# STPedal_Power.net
KiCad netlist of a schematic drawn in Altium Designer
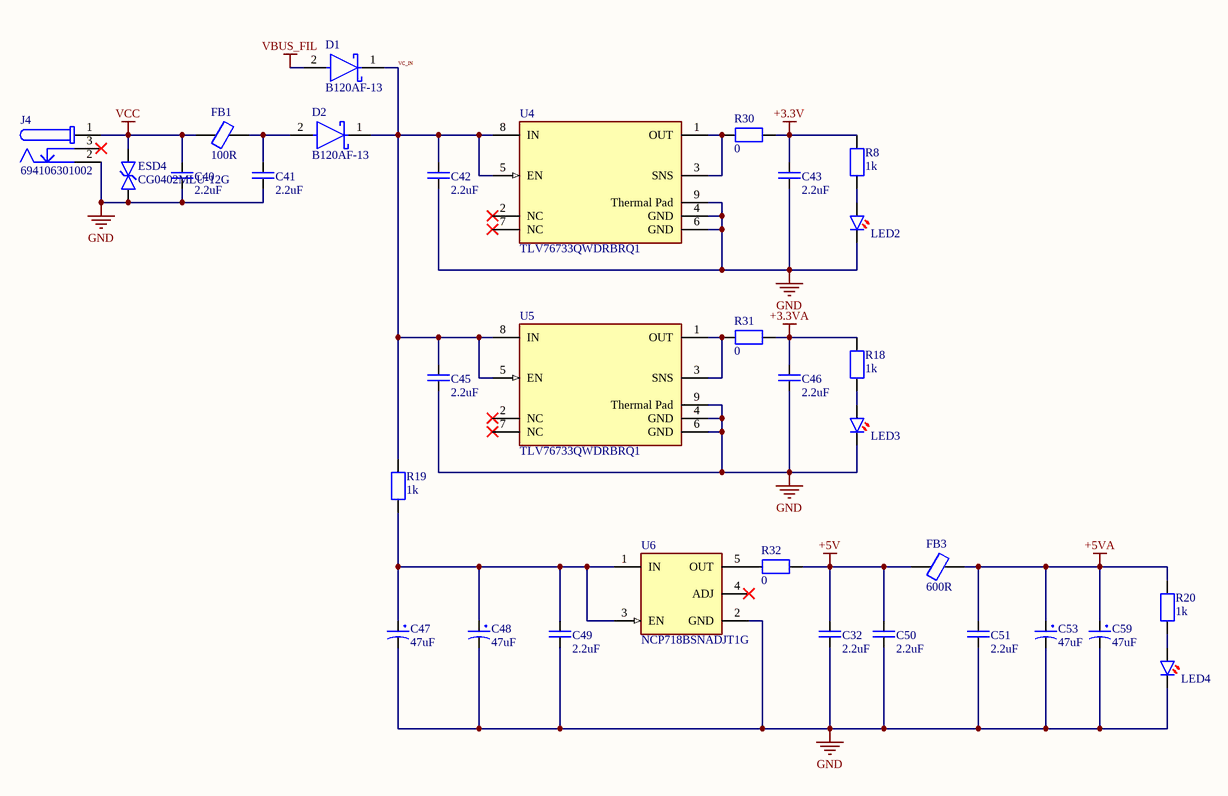
[diagram p0: STPedal_Power.SchDoc]

(export (version "E")
  (design (tool "Eeschema 10.0.6"))
  (components
    (comp (ref "C32")
      (value "2.2uF")
      (footprint "CAPC_0402_1005X55N")
      (description "Capacitor 0402 - 2.2uF +-/10% / 25V")
      (fields
        (field (name "MANUFACTURER") "Samsung Electro-Mechanics")
        (field (name "MPN") "CL05A225MQ5NSNC")
      )
      (libsource (lib "ReekoLib") (part "2.2uF_CAP_0402"))
    )
    (comp (ref "C40")
      (value "2.2uF")
      (footprint "CAPC_0402_1005X55N")
      (description "Capacitor 0402 - 2.2uF +-/10% / 25V")
      (fields
        (field (name "MANUFACTURER") "Samsung Electro-Mechanics")
        (field (name "MPN") "CL05A225MQ5NSNC")
      )
      (libsource (lib "ReekoLib") (part "2.2uF_CAP_0402"))
    )
    (comp (ref "C41")
      (value "2.2uF")
      (footprint "CAPC_0402_1005X55N")
      (description "Capacitor 0402 - 2.2uF +-/10% / 25V")
      (fields
        (field (name "MANUFACTURER") "Samsung Electro-Mechanics")
        (field (name "MPN") "CL05A225MQ5NSNC")
      )
      (libsource (lib "ReekoLib") (part "2.2uF_CAP_0402"))
    )
    (comp (ref "C42")
      (value "2.2uF")
      (footprint "CAPC_0402_1005X55N")
      (description "Capacitor 0402 - 2.2uF +-/10% / 25V")
      (fields
        (field (name "MANUFACTURER") "Samsung Electro-Mechanics")
        (field (name "MPN") "CL05A225MQ5NSNC")
      )
      (libsource (lib "ReekoLib") (part "2.2uF_CAP_0402"))
    )
    (comp (ref "C43")
      (value "2.2uF")
      (footprint "CAPC_0402_1005X55N")
      (description "Capacitor 0402 - 2.2uF +-/10% / 25V")
      (fields
        (field (name "MANUFACTURER") "Samsung Electro-Mechanics")
        (field (name "MPN") "CL05A225MQ5NSNC")
      )
      (libsource (lib "ReekoLib") (part "2.2uF_CAP_0402"))
    )
    (comp (ref "C45")
      (value "2.2uF")
      (footprint "CAPC_0402_1005X55N")
      (description "Capacitor 0402 - 2.2uF +-/10% / 25V")
      (fields
        (field (name "MANUFACTURER") "Samsung Electro-Mechanics")
        (field (name "MPN") "CL05A225MQ5NSNC")
      )
      (libsource (lib "ReekoLib") (part "2.2uF_CAP_0402"))
    )
    (comp (ref "C46")
      (value "2.2uF")
      (footprint "CAPC_0402_1005X55N")
      (description "Capacitor 0402 - 2.2uF +-/10% / 25V")
      (fields
        (field (name "MANUFACTURER") "Samsung Electro-Mechanics")
        (field (name "MPN") "CL05A225MQ5NSNC")
      )
      (libsource (lib "ReekoLib") (part "2.2uF_CAP_0402"))
    )
    (comp (ref "C47")
      (value "47uF")
      (footprint "SMD,D6.3xL5.4mm")
      (fields (field (name "MPN") "RVT1V470M0605"))
      (libsource (lib "ReekoLib") (part "47uF_JLCAP_Elect_D6.3mm"))
    )
    (comp (ref "C48")
      (value "47uF")
      (footprint "SMD,D6.3xL5.4mm")
      (fields (field (name "MPN") "RVT1V470M0605"))
      (libsource (lib "ReekoLib") (part "47uF_JLCAP_Elect_D6.3mm"))
    )
    (comp (ref "C49")
      (value "2.2uF")
      (footprint "CAPC_0402_1005X55N")
      (description "Capacitor 0402 - 2.2uF +-/10% / 25V")
      (fields
        (field (name "MANUFACTURER") "Samsung Electro-Mechanics")
        (field (name "MPN") "CL05A225MQ5NSNC")
      )
      (libsource (lib "ReekoLib") (part "2.2uF_CAP_0402"))
    )
    (comp (ref "C50")
      (value "2.2uF")
      (footprint "CAPC_0402_1005X55N")
      (description "Capacitor 0402 - 2.2uF +-/10% / 25V")
      (fields
        (field (name "MANUFACTURER") "Samsung Electro-Mechanics")
        (field (name "MPN") "CL05A225MQ5NSNC")
      )
      (libsource (lib "ReekoLib") (part "2.2uF_CAP_0402"))
    )
    (comp (ref "C51")
      (value "2.2uF")
      (footprint "CAPC_0402_1005X55N")
      (description "Capacitor 0402 - 2.2uF +-/10% / 25V")
      (fields
        (field (name "MANUFACTURER") "Samsung Electro-Mechanics")
        (field (name "MPN") "CL05A225MQ5NSNC")
      )
      (libsource (lib "ReekoLib") (part "2.2uF_CAP_0402"))
    )
    (comp (ref "C53")
      (value "47uF")
      (footprint "SMD,D6.3xL5.4mm")
      (fields (field (name "MPN") "RVT1V470M0605"))
      (libsource (lib "ReekoLib") (part "47uF_JLCAP_Elect_D6.3mm"))
    )
    (comp (ref "C59")
      (value "47uF")
      (footprint "SMD,D6.3xL5.4mm")
      (fields (field (name "MPN") "RVT1V470M0605"))
      (libsource (lib "ReekoLib") (part "47uF_JLCAP_Elect_D6.3mm"))
    )
    (comp (ref "D1")
      (value "B120AF-13")
      (footprint "FP-SMAF-MFG")
      (description "DIODE SCHOTTKY 20V 1A SMAF")
      (libsource (lib "Altium Content Vault") (part "1d6ec82d83fb6aee721767c19dac4b9"))
    )
    (comp (ref "D2")
      (value "B120AF-13")
      (footprint "FP-SMAF-MFG")
      (description "DIODE SCHOTTKY 20V 1A SMAF")
      (libsource (lib "Altium Content Vault") (part "1d6ec82d83fb6aee721767c19dac4b9"))
    )
    (comp (ref "ESD4")
      (value "CG0402MLU-12G")
      (footprint "DIOC_0402_1005X41N")
      (description "-40℃~+125℃ 0.05pF 1 12V 25V 5nA ESD IEC 61000-4-2 0402 ESD and Surge Protection (TVS/ESD) ROHS")
      (fields (field (name "MANUFACTURER") "BOURNS"))
      (libsource (lib "ReekoLib") (part "CG0402MLU-12G"))
    )
    (comp (ref "FB1")
      (value "100R")
      (footprint "FBC_0805_2012X105N")
      (description "-55℃~+125℃ 1 300mΩ 500mA 600Ω@100MHz ±25% 0805 Ferrite Beads ROHS")
      (fields (field (name "MANUFACTURER") "Sunlord") (field (name "MPN") "GZ2012D601TF"))
      (libsource (lib "ReekoLib") (part "600@100MHz_JLCFB_0805"))
    )
    (comp (ref "FB3")
      (value "600R")
      (footprint "FBC_0805_2012X105N")
      (description "-55℃~+125℃ 1 300mΩ 500mA 600Ω@100MHz ±25% 0805 Ferrite Beads ROHS")
      (fields (field (name "MANUFACTURER") "Sunlord") (field (name "MPN") "GZ2012D601TF"))
      (libsource (lib "ReekoLib") (part "600@100MHz_JLCFB_0805"))
    )
    (comp (ref "J4")
      (value "694106301002")
      (footprint "694106301002")
      (description "DC Power Jack Connector WR-DC, Male, Right Angled, THT, 5 A, 24 V")
      (libsource (lib "Altium Content Vault") (part "DC Power Jack"))
    )
    (comp (ref "LED2")
      (value "LED_Red_JLCD_0603")
      (footprint "LED_0603_1608")
      (fields (field (name "MANUFACTURER") "Hubei KENTO Elec") (field (name "MPN") "KT-0603R"))
      (libsource (lib "ReekoLib") (part "LED_Red_JLCD_0603"))
    )
    (comp (ref "LED3")
      (value "LED_Red_JLCD_0603")
      (footprint "LED_0603_1608")
      (fields (field (name "MANUFACTURER") "Hubei KENTO Elec") (field (name "MPN") "KT-0603R"))
      (libsource (lib "ReekoLib") (part "LED_Red_JLCD_0603"))
    )
    (comp (ref "LED4")
      (value "LED_Red_JLCD_0603")
      (footprint "LED_0603_1608")
      (fields (field (name "MANUFACTURER") "Hubei KENTO Elec") (field (name "MPN") "KT-0603R"))
      (libsource (lib "ReekoLib") (part "LED_Red_JLCD_0603"))
    )
    (comp (ref "R8")
      (value "1k")
      (footprint "RESC_0402_1005X40N")
      (description "Resistor 0402 - 1k")
      (fields (field (name "MANUFACTURER") "UNI-ROYAL(Uniroyal Elec)") (field (name "MPN") "0402WGF1001TCE"))
      (libsource (lib "ReekoLib") (part "1k_JLCRES-0402"))
    )
    (comp (ref "R18")
      (value "1k")
      (footprint "RESC_0402_1005X40N")
      (description "Resistor 0402 - 1k")
      (fields (field (name "MANUFACTURER") "UNI-ROYAL(Uniroyal Elec)") (field (name "MPN") "0402WGF1001TCE"))
      (libsource (lib "ReekoLib") (part "1k_JLCRES-0402"))
    )
    (comp (ref "R19")
      (value "1k")
      (footprint "RESC_0402_1005X40N")
      (description "Resistor 0402 - 100R")
      (libsource (lib "ReekoLib") (part "100R_JLCRES-0402"))
    )
    (comp (ref "R20")
      (value "1k")
      (footprint "RESC_0402_1005X40N")
      (description "Resistor 0402 - 1k")
      (fields (field (name "MANUFACTURER") "UNI-ROYAL(Uniroyal Elec)") (field (name "MPN") "0402WGF1001TCE"))
      (libsource (lib "ReekoLib") (part "1k_JLCRES-0402"))
    )
    (comp (ref "R30")
      (value "0")
      (footprint "RESC_0402_1005X40N")
      (description "-55℃~+155℃ 0Ω 50V 62.5mW Thick Film Resistor ±1% ±800ppm/℃ 0402 Chip Resistor - Surface Mount ROHS")
      (fields (field (name "MANUFACTURER") "UNI-ROYAL(Uniroyal Elec)") (field (name "MPN") "0402WGF0000TCE"))
      (libsource (lib "ReekoLib") (part "0R_JLCRES-0402"))
    )
    (comp (ref "R31")
      (value "0")
      (footprint "RESC_0402_1005X40N")
      (description "-55℃~+155℃ 0Ω 50V 62.5mW Thick Film Resistor ±1% ±800ppm/℃ 0402 Chip Resistor - Surface Mount ROHS")
      (fields (field (name "MANUFACTURER") "UNI-ROYAL(Uniroyal Elec)") (field (name "MPN") "0402WGF0000TCE"))
      (libsource (lib "ReekoLib") (part "0R_JLCRES-0402"))
    )
    (comp (ref "R32")
      (value "0")
      (footprint "RESC_0402_1005X40N")
      (description "-55℃~+155℃ 0Ω 50V 62.5mW Thick Film Resistor ±1% ±800ppm/℃ 0402 Chip Resistor - Surface Mount ROHS")
      (fields (field (name "MANUFACTURER") "UNI-ROYAL(Uniroyal Elec)") (field (name "MPN") "0402WGF0000TCE"))
      (libsource (lib "ReekoLib") (part "0R_JLCRES-0402"))
    )
    (comp (ref "U4")
      (value "TLV76733QWDRBRQ1")
      (footprint "FP-DRB0008J-IPC_C")
      (description "IC OPAMP")
      (libsource (lib "Altium Content Vault") (part "986f8d1759350ee61d4b04c225c65ee"))
    )
    (comp (ref "U5")
      (value "TLV76733QWDRBRQ1")
      (footprint "FP-DRB0008J-IPC_C")
      (description "IC OPAMP")
      (libsource (lib "Altium Content Vault") (part "986f8d1759350ee61d4b04c225c65ee"))
    )
    (comp (ref "U6")
      (value "NCP718BSNADJT1G")
      (footprint "FP-419AE-01-IPC_C")
      (fields
        (field (name "OCTOPART") "https://octopart.com/ncp718bsnadjt1g-on+semiconductor-87658781")
        (field (name "MANUFACTURER PART NUMBER") "NCP718BSN500T1G")
        (field (name "MANUFACTURER") "On Semiconductor")
      )
      (libsource (lib "Altium Content Vault") (part "60dd149d16d23ee5a651c2107203ec7"))
    )
  )
  (nets
    (net (code "1") (name "+3.3V") (class "Default")
      (node (ref "C43") (pin "2") (pintype "passive"))
      (node (ref "R30") (pin "2") (pintype "passive"))
      (node (ref "R8") (pin "2") (pintype "passive"))
    )
    (net (code "2") (name "+3.3VA") (class "Default")
      (node (ref "C46") (pin "2") (pintype "passive"))
      (node (ref "R18") (pin "2") (pintype "passive"))
      (node (ref "R31") (pin "2") (pintype "passive"))
    )
    (net (code "3") (name "+5V") (class "Default")
      (node (ref "C32") (pin "2") (pintype "passive"))
      (node (ref "C50") (pin "2") (pintype "passive"))
      (node (ref "FB3") (pin "1") (pintype "passive"))
      (node (ref "R32") (pin "2") (pintype "passive"))
    )
    (net (code "4") (name "+5VA") (class "Default")
      (node (ref "C51") (pin "2") (pintype "passive"))
      (node (ref "C53") (pin "1") (pintype "passive"))
      (node (ref "C59") (pin "1") (pintype "passive"))
      (node (ref "FB3") (pin "2") (pintype "passive"))
      (node (ref "R20") (pin "1") (pintype "passive"))
    )
    (net (code "5") (name "/VC_IN") (class "Default")
      (node (ref "C42") (pin "2") (pintype "passive"))
      (node (ref "C45") (pin "2") (pintype "passive"))
      (node (ref "D1") (pin "1") (pinfunction "C_1") (pintype "passive"))
      (node (ref "D2") (pin "1") (pinfunction "C_1") (pintype "passive"))
      (node (ref "R19") (pin "2") (pintype "passive"))
      (node (ref "U4") (pin "5") (pinfunction "EN_5") (pintype "input"))
      (node (ref "U4") (pin "8") (pinfunction "IN_8") (pintype "power_in"))
      (node (ref "U5") (pin "5") (pinfunction "EN_5") (pintype "input"))
      (node (ref "U5") (pin "8") (pinfunction "IN_8") (pintype "power_in"))
    )
    (net (code "6") (name "GND") (class "Default")
      (node (ref "C32") (pin "1") (pintype "passive"))
      (node (ref "C40") (pin "1") (pintype "passive"))
      (node (ref "C41") (pin "1") (pintype "passive"))
      (node (ref "C42") (pin "1") (pintype "passive"))
      (node (ref "C43") (pin "1") (pintype "passive"))
      (node (ref "C45") (pin "1") (pintype "passive"))
      (node (ref "C46") (pin "1") (pintype "passive"))
      (node (ref "C47") (pin "2") (pintype "passive"))
      (node (ref "C48") (pin "2") (pintype "passive"))
      (node (ref "C49") (pin "1") (pintype "passive"))
      (node (ref "C50") (pin "1") (pintype "passive"))
      (node (ref "C51") (pin "1") (pintype "passive"))
      (node (ref "C53") (pin "2") (pintype "passive"))
      (node (ref "C59") (pin "2") (pintype "passive"))
      (node (ref "ESD4") (pin "1") (pintype "passive"))
      (node (ref "J4") (pin "2") (pinfunction "2_2") (pintype "passive"))
      (node (ref "LED2") (pin "2") (pintype "passive"))
      (node (ref "LED3") (pin "2") (pintype "passive"))
      (node (ref "LED4") (pin "2") (pintype "passive"))
      (node (ref "U4") (pin "4") (pinfunction "GND_4") (pintype "power_in"))
      (node (ref "U4") (pin "6") (pinfunction "GND_6") (pintype "power_in"))
      (node (ref "U4") (pin "9") (pinfunction "Thermal_Pad_9") (pintype "passive"))
      (node (ref "U5") (pin "4") (pinfunction "GND_4") (pintype "power_in"))
      (node (ref "U5") (pin "6") (pinfunction "GND_6") (pintype "power_in"))
      (node (ref "U5") (pin "9") (pinfunction "Thermal_Pad_9") (pintype "passive"))
      (node (ref "U6") (pin "2") (pinfunction "GND_2") (pintype "power_in"))
    )
    (net (code "7") (name "Net-(D2-A)") (class "Default")
      (node (ref "C41") (pin "2") (pintype "passive"))
      (node (ref "D2") (pin "2") (pinfunction "A_2") (pintype "passive"))
      (node (ref "FB1") (pin "2") (pintype "passive"))
    )
    (net (code "8") (name "Net-(LED2-Pad1)") (class "Default")
      (node (ref "LED2") (pin "1") (pintype "passive"))
      (node (ref "R8") (pin "1") (pintype "passive"))
    )
    (net (code "9") (name "Net-(LED3-Pad1)") (class "Default")
      (node (ref "LED3") (pin "1") (pintype "passive"))
      (node (ref "R18") (pin "1") (pintype "passive"))
    )
    (net (code "10") (name "Net-(LED4-Pad1)") (class "Default")
      (node (ref "LED4") (pin "1") (pintype "passive"))
      (node (ref "R20") (pin "2") (pintype "passive"))
    )
    (net (code "11") (name "Net-(U4-OUT)") (class "Default")
      (node (ref "R30") (pin "1") (pintype "passive"))
      (node (ref "U4") (pin "1") (pinfunction "OUT_1") (pintype "power_in"))
      (node (ref "U4") (pin "3") (pinfunction "SNS_3") (pintype "passive"))
    )
    (net (code "12") (name "Net-(U5-OUT)") (class "Default")
      (node (ref "R31") (pin "1") (pintype "passive"))
      (node (ref "U5") (pin "1") (pinfunction "OUT_1") (pintype "power_in"))
      (node (ref "U5") (pin "3") (pinfunction "SNS_3") (pintype "passive"))
    )
    (net (code "13") (name "Net-(U6-EN)") (class "Default")
      (node (ref "C47") (pin "1") (pintype "passive"))
      (node (ref "C48") (pin "1") (pintype "passive"))
      (node (ref "C49") (pin "2") (pintype "passive"))
      (node (ref "R19") (pin "1") (pintype "passive"))
      (node (ref "U6") (pin "1") (pinfunction "IN_1") (pintype "power_in"))
      (node (ref "U6") (pin "3") (pinfunction "EN_3") (pintype "input"))
    )
    (net (code "14") (name "Net-(U6-OUT)") (class "Default")
      (node (ref "R32") (pin "1") (pintype "passive"))
      (node (ref "U6") (pin "5") (pinfunction "OUT_5") (pintype "power_in"))
    )
    (net (code "15") (name "VBUS_FIL") (class "Default")
      (node (ref "D1") (pin "2") (pinfunction "A_2") (pintype "passive"))
    )
    (net (code "16") (name "VCC") (class "Default")
      (node (ref "C40") (pin "2") (pintype "passive"))
      (node (ref "ESD4") (pin "2") (pintype "passive"))
      (node (ref "FB1") (pin "1") (pintype "passive"))
      (node (ref "J4") (pin "1") (pinfunction "1_1") (pintype "passive"))
    )
    (net (code "17") (name "unconnected-(J4-Pad3)") (class "Default")
      (node (ref "J4") (pin "3") (pinfunction "3_3") (pintype "passive+no_connect"))
    )
    (net (code "18") (name "unconnected-(U4-NC-Pad2)") (class "Default")
      (node (ref "U4") (pin "2") (pinfunction "NC_2") (pintype "passive+no_connect"))
    )
    (net (code "19") (name "unconnected-(U4-NC-Pad7)") (class "Default")
      (node (ref "U4") (pin "7") (pinfunction "NC_7") (pintype "passive+no_connect"))
    )
    (net (code "20") (name "unconnected-(U5-NC-Pad2)") (class "Default")
      (node (ref "U5") (pin "2") (pinfunction "NC_2") (pintype "passive+no_connect"))
    )
    (net (code "21") (name "unconnected-(U5-NC-Pad7)") (class "Default")
      (node (ref "U5") (pin "7") (pinfunction "NC_7") (pintype "passive+no_connect"))
    )
    (net (code "22") (name "unconnected-(U6-ADJ-Pad4)") (class "Default")
      (node (ref "U6") (pin "4") (pinfunction "ADJ_4") (pintype "passive+no_connect"))
    )
  )
)
